# dual-h-v1.net
KiCad netlist of a schematic drawn in EAGLE
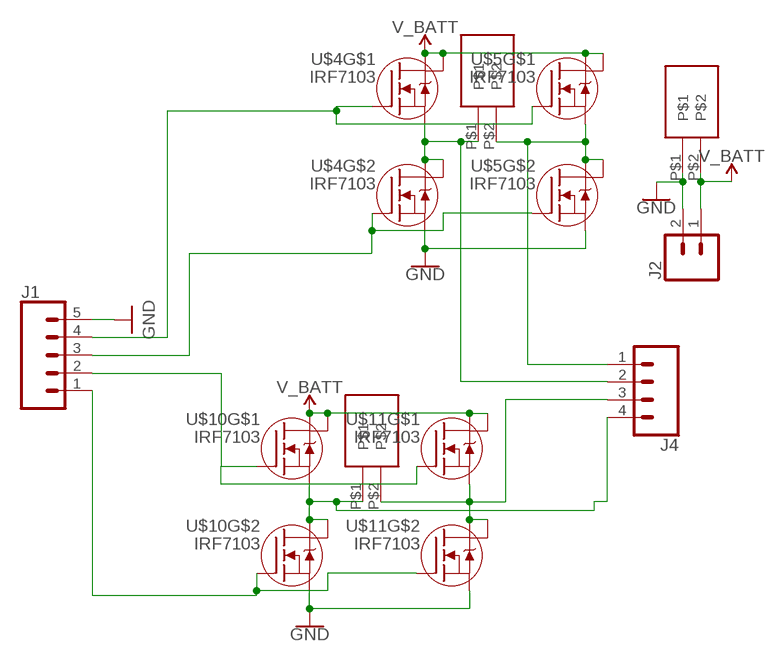
[diagram p0: schematic, sheet 1]

(export (version "E")
  (design (tool "Eeschema 10.0.6"))
  (components
    (comp (ref "J1")
      (value "CONN_05")
      (footprint "eagle-import:1X05")
      (libsource (lib "eagle-import") (part "CONN_05"))
    )
    (comp (ref "J2")
      (value "CONN_02")
      (footprint "eagle-import:1X02")
      (libsource (lib "eagle-import") (part "CONN_02"))
    )
    (comp (ref "J4")
      (value "CONN_04")
      (footprint "eagle-import:1X04")
      (libsource (lib "eagle-import") (part "CONN_04"))
    )
    (comp (ref "U$1")
      (value "SPRING-TERMINAL")
      (footprint "eagle-import:SPRING-TERMINAL")
      (libsource (lib "eagle-import") (part "SPRING-TERMINAL"))
    )
    (comp (ref "U$4")
      (value "IRF7103")
      (footprint "eagle-import:SO8-2")
      (libsource (lib "eagle-import") (part "IRF7103"))
    )
    (comp (ref "U$5")
      (value "IRF7103")
      (footprint "eagle-import:SO8-2")
      (libsource (lib "eagle-import") (part "IRF7103"))
    )
    (comp (ref "U$6")
      (value "SPRING-TERMINAL")
      (footprint "eagle-import:SPRING-TERMINAL")
      (libsource (lib "eagle-import") (part "SPRING-TERMINAL"))
    )
    (comp (ref "U$10")
      (value "IRF7103")
      (footprint "eagle-import:SO8-2")
      (libsource (lib "eagle-import") (part "IRF7103"))
    )
    (comp (ref "U$11")
      (value "IRF7103")
      (footprint "eagle-import:SO8-2")
      (libsource (lib "eagle-import") (part "IRF7103"))
    )
    (comp (ref "U$12")
      (value "SPRING-TERMINAL")
      (footprint "eagle-import:SPRING-TERMINAL")
      (libsource (lib "eagle-import") (part "SPRING-TERMINAL"))
    )
  )
  (nets
    (net (code "1") (name "GND") (class "Default")
      (node (ref "J1") (pin "5") (pinfunction "5_5") (pintype "passive"))
      (node (ref "J2") (pin "2") (pinfunction "2_2") (pintype "passive"))
      (node (ref "U$1") (pin "P$1") (pinfunction "P$1_P$1") (pintype "bidirectional"))
      (node (ref "U$10") (pin "3") (pinfunction "S_3") (pintype "bidirectional"))
      (node (ref "U$11") (pin "3") (pinfunction "S_3") (pintype "bidirectional"))
      (node (ref "U$4") (pin "3") (pinfunction "S_3") (pintype "bidirectional"))
      (node (ref "U$5") (pin "3") (pinfunction "S_3") (pintype "bidirectional"))
    )
    (net (code "2") (name "Net-(U$4A-G)") (class "Default")
      (node (ref "J1") (pin "4") (pinfunction "4_4") (pintype "passive"))
      (node (ref "U$4") (pin "2") (pinfunction "G_2") (pintype "bidirectional"))
      (node (ref "U$5") (pin "2") (pinfunction "G_2") (pintype "bidirectional"))
    )
    (net (code "3") (name "Net-(U$4A-S)") (class "Default")
      (node (ref "J4") (pin "2") (pinfunction "2_2") (pintype "passive"))
      (node (ref "U$4") (pin "1") (pinfunction "S_1") (pintype "bidirectional"))
      (node (ref "U$4") (pin "5") (pinfunction "D_5") (pintype "bidirectional"))
      (node (ref "U$4") (pin "6") (pinfunction "D_6") (pintype "bidirectional"))
      (node (ref "U$6") (pin "P$1") (pinfunction "P$1_P$1") (pintype "bidirectional"))
    )
    (net (code "4") (name "Net-(U$4B-G)") (class "Default")
      (node (ref "J1") (pin "3") (pinfunction "3_3") (pintype "passive"))
      (node (ref "U$4") (pin "4") (pinfunction "G_4") (pintype "bidirectional"))
      (node (ref "U$5") (pin "4") (pinfunction "G_4") (pintype "bidirectional"))
    )
    (net (code "5") (name "Net-(U$5A-S)") (class "Default")
      (node (ref "J4") (pin "1") (pinfunction "1_1") (pintype "passive"))
      (node (ref "U$5") (pin "1") (pinfunction "S_1") (pintype "bidirectional"))
      (node (ref "U$5") (pin "5") (pinfunction "D_5") (pintype "bidirectional"))
      (node (ref "U$5") (pin "6") (pinfunction "D_6") (pintype "bidirectional"))
      (node (ref "U$6") (pin "P$2") (pinfunction "P$2_P$2") (pintype "bidirectional"))
    )
    (net (code "6") (name "Net-(U$10A-G)") (class "Default")
      (node (ref "J1") (pin "2") (pinfunction "2_2") (pintype "passive"))
      (node (ref "U$10") (pin "2") (pinfunction "G_2") (pintype "bidirectional"))
      (node (ref "U$11") (pin "2") (pinfunction "G_2") (pintype "bidirectional"))
    )
    (net (code "7") (name "Net-(U$10A-S)") (class "Default")
      (node (ref "J4") (pin "4") (pinfunction "4_4") (pintype "passive"))
      (node (ref "U$10") (pin "1") (pinfunction "S_1") (pintype "bidirectional"))
      (node (ref "U$10") (pin "5") (pinfunction "D_5") (pintype "bidirectional"))
      (node (ref "U$10") (pin "6") (pinfunction "D_6") (pintype "bidirectional"))
      (node (ref "U$12") (pin "P$1") (pinfunction "P$1_P$1") (pintype "bidirectional"))
    )
    (net (code "8") (name "Net-(U$10B-G)") (class "Default")
      (node (ref "J1") (pin "1") (pinfunction "1_1") (pintype "passive"))
      (node (ref "U$10") (pin "4") (pinfunction "G_4") (pintype "bidirectional"))
      (node (ref "U$11") (pin "4") (pinfunction "G_4") (pintype "bidirectional"))
    )
    (net (code "9") (name "Net-(U$11A-S)") (class "Default")
      (node (ref "J4") (pin "3") (pinfunction "3_3") (pintype "passive"))
      (node (ref "U$11") (pin "1") (pinfunction "S_1") (pintype "bidirectional"))
      (node (ref "U$11") (pin "5") (pinfunction "D_5") (pintype "bidirectional"))
      (node (ref "U$11") (pin "6") (pinfunction "D_6") (pintype "bidirectional"))
      (node (ref "U$12") (pin "P$2") (pinfunction "P$2_P$2") (pintype "bidirectional"))
    )
    (net (code "10") (name "V_BATT") (class "Default")
      (node (ref "J2") (pin "1") (pinfunction "1_1") (pintype "passive"))
      (node (ref "U$1") (pin "P$2") (pinfunction "P$2_P$2") (pintype "bidirectional"))
      (node (ref "U$10") (pin "7") (pinfunction "D_7") (pintype "bidirectional"))
      (node (ref "U$10") (pin "8") (pinfunction "D_8") (pintype "bidirectional"))
      (node (ref "U$11") (pin "7") (pinfunction "D_7") (pintype "bidirectional"))
      (node (ref "U$11") (pin "8") (pinfunction "D_8") (pintype "bidirectional"))
      (node (ref "U$4") (pin "7") (pinfunction "D_7") (pintype "bidirectional"))
      (node (ref "U$4") (pin "8") (pinfunction "D_8") (pintype "bidirectional"))
      (node (ref "U$5") (pin "7") (pinfunction "D_7") (pintype "bidirectional"))
      (node (ref "U$5") (pin "8") (pinfunction "D_8") (pintype "bidirectional"))
    )
  )
)
